# amp-LNA-BGB7XXL7ESD.net
KiCad netlist of a schematic drawn in EAGLE
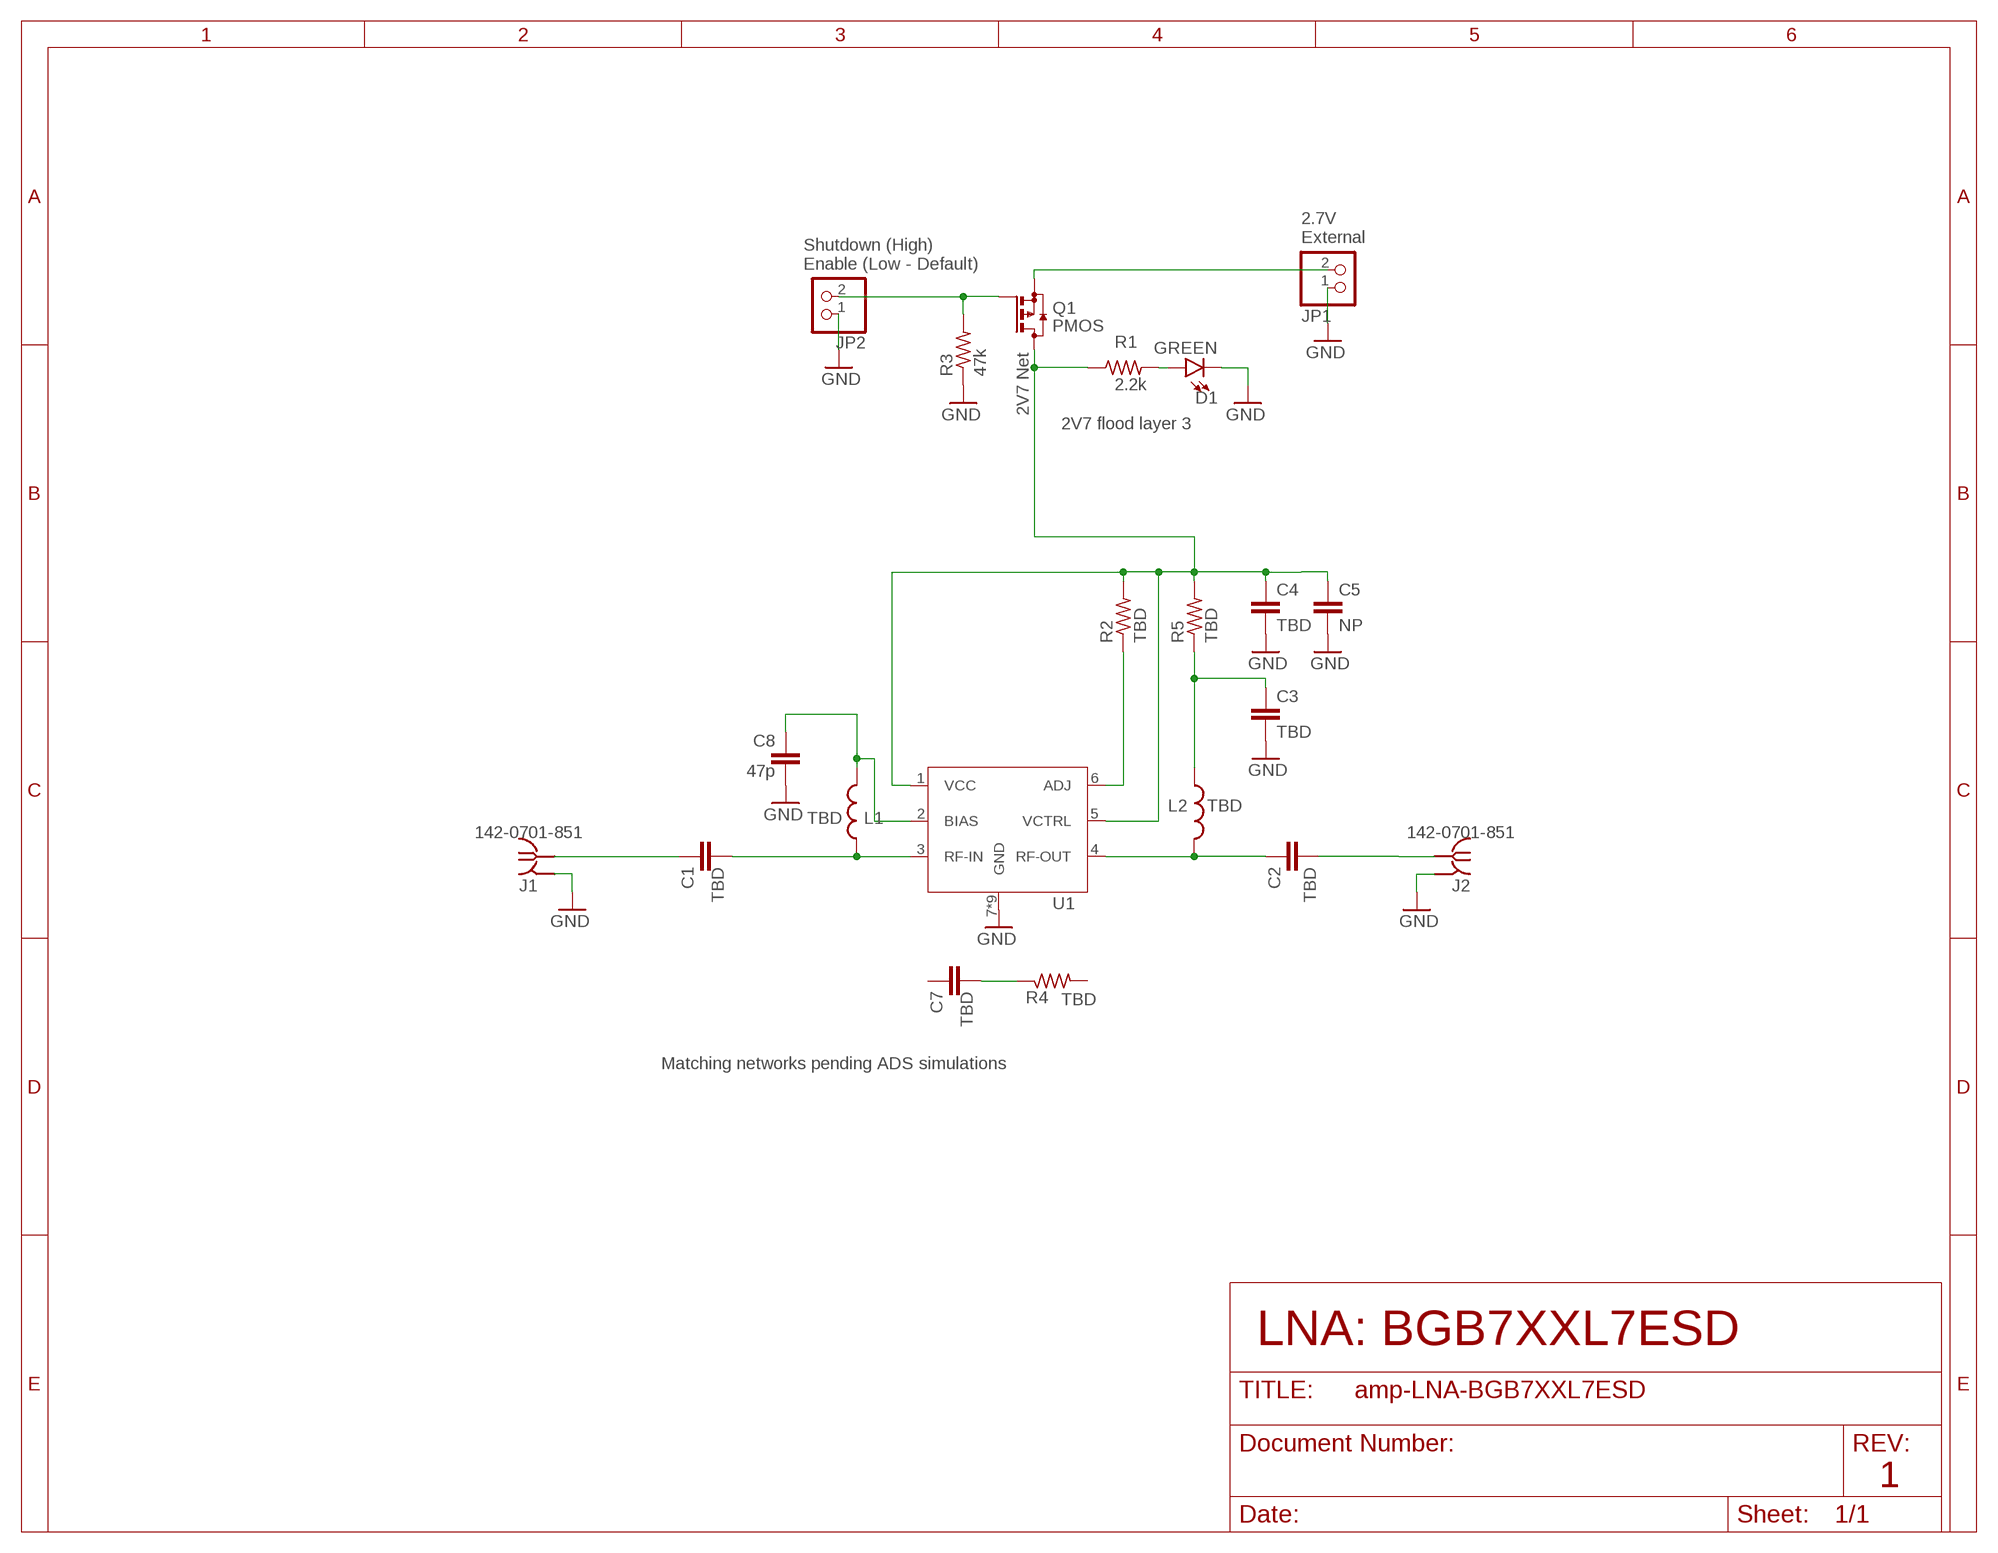
[diagram p0: schematic, sheet 1]

(export (version "E")
  (design (tool "Eeschema 10.0.6"))
  (components
    (comp (ref "C1")
      (value "TBD")
      (footprint "eagle-import:.0402-C-NOSILK")
      (libsource (lib "eagle-import") (part "C-EU0402-C-NOSILK"))
    )
    (comp (ref "C2")
      (value "TBD")
      (footprint "eagle-import:.0402-C-NOSILK")
      (libsource (lib "eagle-import") (part "C-EU0402-C-NOSILK"))
    )
    (comp (ref "C3")
      (value "TBD")
      (footprint "eagle-import:.0402-C-NOSILK")
      (libsource (lib "eagle-import") (part "C-EU0402-C-NOSILK"))
    )
    (comp (ref "C4")
      (value "TBD")
      (footprint "eagle-import:.0402-C-NOSILK")
      (libsource (lib "eagle-import") (part "C-EU0402-C-NOSILK"))
    )
    (comp (ref "C5")
      (value "NP")
      (footprint "eagle-import:.0603-C-NOSILK")
      (libsource (lib "eagle-import") (part "C-EU0603-C-NOSILK"))
    )
    (comp (ref "C7")
      (value "TBD")
      (footprint "eagle-import:.0402-C-NOSILK")
      (libsource (lib "eagle-import") (part "C-EU0402-C-NOSILK"))
    )
    (comp (ref "C8")
      (value "47p")
      (footprint "eagle-import:.0402-C-NOSILK")
      (libsource (lib "eagle-import") (part "C-EU0402-C-NOSILK"))
    )
    (comp (ref "D1")
      (value "GREEN")
      (footprint "eagle-import:LED-0603")
      (libsource (lib "eagle-import") (part "LED-GREEN0603"))
    )
    (comp (ref "J1")
      (value "142-0701-851")
      (footprint "eagle-import:142-0701-851")
      (libsource (lib "eagle-import") (part "142-0701-851"))
    )
    (comp (ref "J2")
      (value "142-0701-851")
      (footprint "eagle-import:142-0701-851")
      (libsource (lib "eagle-import") (part "142-0701-851"))
    )
    (comp (ref "JP1")
      (value "PINHD-1X2")
      (footprint "eagle-import:1X02")
      (libsource (lib "eagle-import") (part "PINHD-1X2"))
    )
    (comp (ref "JP2")
      (value "PINHD-1X2")
      (footprint "eagle-import:1X02")
      (libsource (lib "eagle-import") (part "PINHD-1X2"))
    )
    (comp (ref "L1")
      (value "TBD")
      (footprint "eagle-import:.0402-C-NOSILK")
      (libsource (lib "eagle-import") (part "L-US0402-C-NOSILK"))
    )
    (comp (ref "L2")
      (value "TBD")
      (footprint "eagle-import:.0402-C-NOSILK")
      (libsource (lib "eagle-import") (part "L-US0402-C-NOSILK"))
    )
    (comp (ref "Q1")
      (value "PMOS")
      (footprint "eagle-import:SOT23")
      (libsource (lib "eagle-import") (part "BSS84"))
    )
    (comp (ref "R1")
      (value "2.2k")
      (footprint "eagle-import:.0603-B-NOSILK")
      (libsource (lib "eagle-import") (part "R-US_0603-B-NOSILK"))
    )
    (comp (ref "R2")
      (value "TBD")
      (footprint "eagle-import:.0603-B-NOSILK")
      (libsource (lib "eagle-import") (part "R-US_0603-B-NOSILK"))
    )
    (comp (ref "R3")
      (value "47k")
      (footprint "eagle-import:.0402-B-NOSILK")
      (libsource (lib "eagle-import") (part "R-US_0402-B-NOSILK"))
    )
    (comp (ref "R4")
      (value "TBD")
      (footprint "eagle-import:.0402-C-NOSILK")
      (libsource (lib "eagle-import") (part "R-US_0402-C-NOSILK"))
    )
    (comp (ref "R5")
      (value "TBD")
      (footprint "eagle-import:.0402-C-NOSILK")
      (libsource (lib "eagle-import") (part "R-US_0402-C-NOSILK"))
    )
    (comp (ref "U1")
      (value "BGB7XXL7ESD")
      (footprint "eagle-import:BGB7XXL7ESD")
      (libsource (lib "eagle-import") (part "BGB7XXL7ESD"))
    )
  )
  (nets
    (net (code "1") (name "GND") (class "Default")
      (node (ref "C3") (pin "2") (pinfunction "2_2") (pintype "passive"))
      (node (ref "C4") (pin "2") (pinfunction "2_2") (pintype "passive"))
      (node (ref "C5") (pin "2") (pinfunction "2_2") (pintype "passive"))
      (node (ref "C8") (pin "2") (pinfunction "2_2") (pintype "passive"))
      (node (ref "D1") (pin "C") (pinfunction "C_C") (pintype "passive"))
      (node (ref "J1") (pin "GND1") (pinfunction "GND_GND1") (pintype "bidirectional"))
      (node (ref "J1") (pin "GND2") (pinfunction "GND_GND2") (pintype "bidirectional"))
      (node (ref "J1") (pin "GND3") (pinfunction "GND_GND3") (pintype "bidirectional"))
      (node (ref "J1") (pin "GND4") (pinfunction "GND_GND4") (pintype "bidirectional"))
      (node (ref "J2") (pin "GND1") (pinfunction "GND_GND1") (pintype "bidirectional"))
      (node (ref "J2") (pin "GND2") (pinfunction "GND_GND2") (pintype "bidirectional"))
      (node (ref "J2") (pin "GND3") (pinfunction "GND_GND3") (pintype "bidirectional"))
      (node (ref "J2") (pin "GND4") (pinfunction "GND_GND4") (pintype "bidirectional"))
      (node (ref "JP1") (pin "1") (pinfunction "1_1") (pintype "passive"))
      (node (ref "JP2") (pin "1") (pinfunction "1_1") (pintype "passive"))
      (node (ref "R3") (pin "1") (pinfunction "1_1") (pintype "passive"))
      (node (ref "U1") (pin "10") (pinfunction "GND_10") (pintype "power_in"))
      (node (ref "U1") (pin "11") (pinfunction "GND_11") (pintype "power_in"))
      (node (ref "U1") (pin "12") (pinfunction "GND_12") (pintype "power_in"))
      (node (ref "U1") (pin "13") (pinfunction "GND_13") (pintype "power_in"))
      (node (ref "U1") (pin "14") (pinfunction "GND_14") (pintype "power_in"))
      (node (ref "U1") (pin "15") (pinfunction "GND_15") (pintype "power_in"))
      (node (ref "U1") (pin "7") (pinfunction "GND_7") (pintype "power_in"))
      (node (ref "U1") (pin "8") (pinfunction "GND_8") (pintype "power_in"))
      (node (ref "U1") (pin "9") (pinfunction "GND_9") (pintype "power_in"))
    )
    (net (code "2") (name "Net-(C3-Pad1)") (class "Default")
      (node (ref "C3") (pin "1") (pinfunction "1_1") (pintype "passive"))
      (node (ref "L2") (pin "1") (pinfunction "1_1") (pintype "passive"))
      (node (ref "R5") (pin "1") (pinfunction "1_1") (pintype "passive"))
    )
    (net (code "3") (name "Net-(C7-Pad2)") (class "Default")
      (node (ref "C7") (pin "2") (pinfunction "2_2") (pintype "passive"))
      (node (ref "R4") (pin "1") (pinfunction "1_1") (pintype "passive"))
    )
    (net (code "4") (name "Net-(D1-PadA)") (class "Default")
      (node (ref "D1") (pin "A") (pinfunction "A_A") (pintype "passive"))
      (node (ref "R1") (pin "2") (pinfunction "2_2") (pintype "passive"))
    )
    (net (code "5") (name "Net-(J1-RF)") (class "Default")
      (node (ref "C1") (pin "1") (pinfunction "1_1") (pintype "passive"))
      (node (ref "J1") (pin "RF1") (pinfunction "RF_RF1") (pintype "bidirectional"))
    )
    (net (code "6") (name "Net-(J2-RF)") (class "Default")
      (node (ref "C2") (pin "2") (pinfunction "2_2") (pintype "passive"))
      (node (ref "J2") (pin "RF1") (pinfunction "RF_RF1") (pintype "bidirectional"))
    )
    (net (code "7") (name "Net-(Q1-D)") (class "Default")
      (node (ref "C4") (pin "1") (pinfunction "1_1") (pintype "passive"))
      (node (ref "C5") (pin "1") (pinfunction "1_1") (pintype "passive"))
      (node (ref "Q1") (pin "3") (pinfunction "D_3") (pintype "passive"))
      (node (ref "R1") (pin "1") (pinfunction "1_1") (pintype "passive"))
      (node (ref "R2") (pin "2") (pinfunction "2_2") (pintype "passive"))
      (node (ref "R5") (pin "2") (pinfunction "2_2") (pintype "passive"))
      (node (ref "U1") (pin "1") (pinfunction "VCC_1") (pintype "power_in"))
      (node (ref "U1") (pin "5") (pinfunction "VCTRL_5") (pintype "input"))
    )
    (net (code "8") (name "Net-(Q1-G)") (class "Default")
      (node (ref "JP2") (pin "2") (pinfunction "2_2") (pintype "passive"))
      (node (ref "Q1") (pin "1") (pinfunction "G_1") (pintype "passive"))
      (node (ref "R3") (pin "2") (pinfunction "2_2") (pintype "passive"))
    )
    (net (code "9") (name "Net-(Q1-S)") (class "Default")
      (node (ref "JP1") (pin "2") (pinfunction "2_2") (pintype "passive"))
      (node (ref "Q1") (pin "2") (pinfunction "S_2") (pintype "passive"))
    )
    (net (code "10") (name "Net-(U1-ADJ)") (class "Default")
      (node (ref "R2") (pin "1") (pinfunction "1_1") (pintype "passive"))
      (node (ref "U1") (pin "6") (pinfunction "ADJ_6") (pintype "power_in"))
    )
    (net (code "11") (name "Net-(U1-BIAS)") (class "Default")
      (node (ref "C8") (pin "1") (pinfunction "1_1") (pintype "passive"))
      (node (ref "L1") (pin "2") (pinfunction "2_2") (pintype "passive"))
      (node (ref "U1") (pin "2") (pinfunction "BIAS_2") (pintype "bidirectional"))
    )
    (net (code "12") (name "Net-(U1-RF-IN)") (class "Default")
      (node (ref "C1") (pin "2") (pinfunction "2_2") (pintype "passive"))
      (node (ref "L1") (pin "1") (pinfunction "1_1") (pintype "passive"))
      (node (ref "U1") (pin "3") (pinfunction "RF-IN_3") (pintype "input"))
    )
    (net (code "13") (name "Net-(U1-RF-OUT)") (class "Default")
      (node (ref "C2") (pin "1") (pinfunction "1_1") (pintype "passive"))
      (node (ref "L2") (pin "2") (pinfunction "2_2") (pintype "passive"))
      (node (ref "U1") (pin "4") (pinfunction "RF-OUT_4") (pintype "output"))
    )
    (net (code "14") (name "unconnected-(C7-Pad1)") (class "Default")
      (node (ref "C7") (pin "1") (pinfunction "1_1") (pintype "passive"))
    )
    (net (code "15") (name "unconnected-(R4-Pad2)") (class "Default")
      (node (ref "R4") (pin "2") (pinfunction "2_2") (pintype "passive"))
    )
  )
)
